# LED_Connectors.net
KiCad netlist of a schematic drawn in Altium Designer
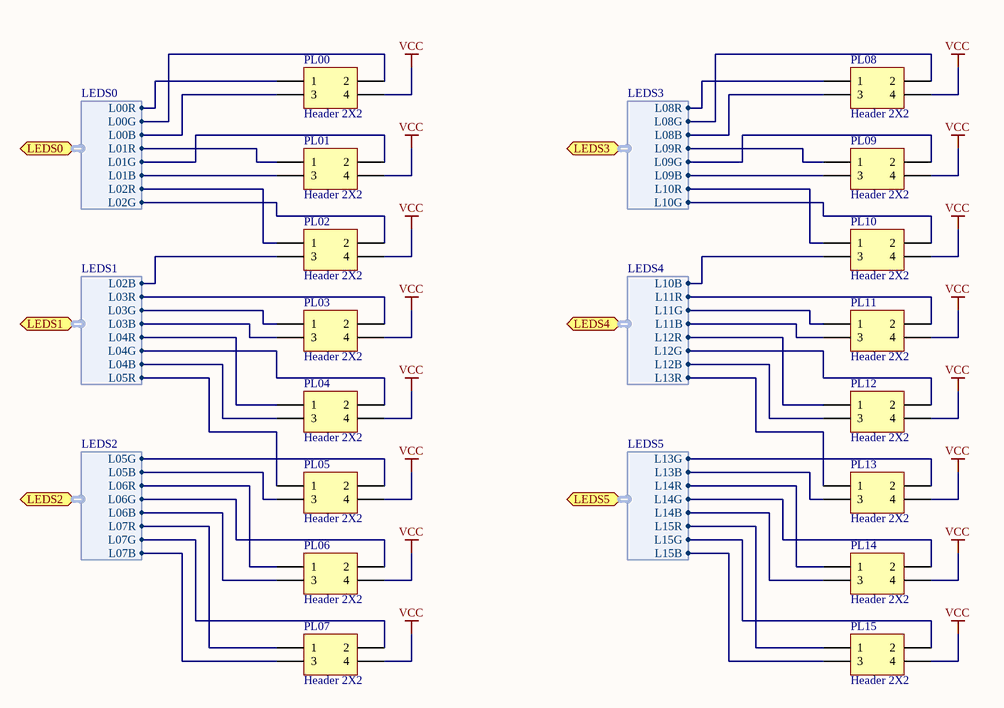
[diagram p0: LED Connectors.SchDoc]

(export (version "E")
  (design (tool "Eeschema 10.0.6"))
  (components
    (comp (ref "PL00")
      (value "Header 2X2")
      (footprint "HDR2X2")
      (description "Header, 2-Pin, Dual row")
      (fields (field (name "PUBLISHER") "Altium Limited"))
      (libsource (lib "Miscellaneous Connectors") (part "Header 2X2"))
    )
    (comp (ref "PL01")
      (value "Header 2X2")
      (footprint "HDR2X2")
      (description "Header, 2-Pin, Dual row")
      (fields (field (name "PUBLISHER") "Altium Limited"))
      (libsource (lib "Miscellaneous Connectors") (part "Header 2X2"))
    )
    (comp (ref "PL02")
      (value "Header 2X2")
      (footprint "HDR2X2")
      (description "Header, 2-Pin, Dual row")
      (fields (field (name "PUBLISHER") "Altium Limited"))
      (libsource (lib "Miscellaneous Connectors") (part "Header 2X2"))
    )
    (comp (ref "PL03")
      (value "Header 2X2")
      (footprint "HDR2X2")
      (description "Header, 2-Pin, Dual row")
      (fields (field (name "PUBLISHER") "Altium Limited"))
      (libsource (lib "Miscellaneous Connectors") (part "Header 2X2"))
    )
    (comp (ref "PL04")
      (value "Header 2X2")
      (footprint "HDR2X2")
      (description "Header, 2-Pin, Dual row")
      (fields (field (name "PUBLISHER") "Altium Limited"))
      (libsource (lib "Miscellaneous Connectors") (part "Header 2X2"))
    )
    (comp (ref "PL05")
      (value "Header 2X2")
      (footprint "HDR2X2")
      (description "Header, 2-Pin, Dual row")
      (fields (field (name "PUBLISHER") "Altium Limited"))
      (libsource (lib "Miscellaneous Connectors") (part "Header 2X2"))
    )
    (comp (ref "PL06")
      (value "Header 2X2")
      (footprint "HDR2X2")
      (description "Header, 2-Pin, Dual row")
      (fields (field (name "PUBLISHER") "Altium Limited"))
      (libsource (lib "Miscellaneous Connectors") (part "Header 2X2"))
    )
    (comp (ref "PL07")
      (value "Header 2X2")
      (footprint "HDR2X2")
      (description "Header, 2-Pin, Dual row")
      (fields (field (name "PUBLISHER") "Altium Limited"))
      (libsource (lib "Miscellaneous Connectors") (part "Header 2X2"))
    )
    (comp (ref "PL08")
      (value "Header 2X2")
      (footprint "HDR2X2")
      (description "Header, 2-Pin, Dual row")
      (fields (field (name "PUBLISHER") "Altium Limited"))
      (libsource (lib "Miscellaneous Connectors") (part "Header 2X2"))
    )
    (comp (ref "PL09")
      (value "Header 2X2")
      (footprint "HDR2X2")
      (description "Header, 2-Pin, Dual row")
      (fields (field (name "PUBLISHER") "Altium Limited"))
      (libsource (lib "Miscellaneous Connectors") (part "Header 2X2"))
    )
    (comp (ref "PL10")
      (value "Header 2X2")
      (footprint "HDR2X2")
      (description "Header, 2-Pin, Dual row")
      (fields (field (name "PUBLISHER") "Altium Limited"))
      (libsource (lib "Miscellaneous Connectors") (part "Header 2X2"))
    )
    (comp (ref "PL11")
      (value "Header 2X2")
      (footprint "HDR2X2")
      (description "Header, 2-Pin, Dual row")
      (fields (field (name "PUBLISHER") "Altium Limited"))
      (libsource (lib "Miscellaneous Connectors") (part "Header 2X2"))
    )
    (comp (ref "PL12")
      (value "Header 2X2")
      (footprint "HDR2X2")
      (description "Header, 2-Pin, Dual row")
      (fields (field (name "PUBLISHER") "Altium Limited"))
      (libsource (lib "Miscellaneous Connectors") (part "Header 2X2"))
    )
    (comp (ref "PL13")
      (value "Header 2X2")
      (footprint "HDR2X2")
      (description "Header, 2-Pin, Dual row")
      (fields (field (name "PUBLISHER") "Altium Limited"))
      (libsource (lib "Miscellaneous Connectors") (part "Header 2X2"))
    )
    (comp (ref "PL14")
      (value "Header 2X2")
      (footprint "HDR2X2")
      (description "Header, 2-Pin, Dual row")
      (fields (field (name "PUBLISHER") "Altium Limited"))
      (libsource (lib "Miscellaneous Connectors") (part "Header 2X2"))
    )
    (comp (ref "PL15")
      (value "Header 2X2")
      (footprint "HDR2X2")
      (description "Header, 2-Pin, Dual row")
      (fields (field (name "PUBLISHER") "Altium Limited"))
      (libsource (lib "Miscellaneous Connectors") (part "Header 2X2"))
    )
  )
  (nets
    (net (code "7") (name "/L00B") (class "Default")
      (node (ref "PL00") (pin "3") (pinfunction "3_3") (pintype "passive"))
    )
    (net (code "8") (name "/L00G") (class "Default")
      (node (ref "PL00") (pin "2") (pinfunction "2_2") (pintype "passive"))
    )
    (net (code "9") (name "/L00R") (class "Default")
      (node (ref "PL00") (pin "1") (pinfunction "1_1") (pintype "passive"))
    )
    (net (code "10") (name "/L01B") (class "Default")
      (node (ref "PL01") (pin "3") (pinfunction "3_3") (pintype "passive"))
    )
    (net (code "11") (name "/L01G") (class "Default")
      (node (ref "PL01") (pin "2") (pinfunction "2_2") (pintype "passive"))
    )
    (net (code "12") (name "/L01R") (class "Default")
      (node (ref "PL01") (pin "1") (pinfunction "1_1") (pintype "passive"))
    )
    (net (code "13") (name "/L02B") (class "Default")
      (node (ref "PL02") (pin "3") (pinfunction "3_3") (pintype "passive"))
    )
    (net (code "14") (name "/L02G") (class "Default")
      (node (ref "PL02") (pin "2") (pinfunction "2_2") (pintype "passive"))
    )
    (net (code "15") (name "/L02R") (class "Default")
      (node (ref "PL02") (pin "1") (pinfunction "1_1") (pintype "passive"))
    )
    (net (code "16") (name "/L03B") (class "Default")
      (node (ref "PL03") (pin "3") (pinfunction "3_3") (pintype "passive"))
    )
    (net (code "17") (name "/L03G") (class "Default")
      (node (ref "PL03") (pin "1") (pinfunction "1_1") (pintype "passive"))
    )
    (net (code "18") (name "/L03R") (class "Default")
      (node (ref "PL03") (pin "2") (pinfunction "2_2") (pintype "passive"))
    )
    (net (code "19") (name "/L04B") (class "Default")
      (node (ref "PL04") (pin "3") (pinfunction "3_3") (pintype "passive"))
    )
    (net (code "20") (name "/L04G") (class "Default")
      (node (ref "PL04") (pin "2") (pinfunction "2_2") (pintype "passive"))
    )
    (net (code "21") (name "/L04R") (class "Default")
      (node (ref "PL04") (pin "1") (pinfunction "1_1") (pintype "passive"))
    )
    (net (code "22") (name "/L05B") (class "Default")
      (node (ref "PL05") (pin "3") (pinfunction "3_3") (pintype "passive"))
    )
    (net (code "23") (name "/L05G") (class "Default")
      (node (ref "PL05") (pin "2") (pinfunction "2_2") (pintype "passive"))
    )
    (net (code "24") (name "/L05R") (class "Default")
      (node (ref "PL05") (pin "1") (pinfunction "1_1") (pintype "passive"))
    )
    (net (code "25") (name "/L06B") (class "Default")
      (node (ref "PL06") (pin "3") (pinfunction "3_3") (pintype "passive"))
    )
    (net (code "26") (name "/L06G") (class "Default")
      (node (ref "PL06") (pin "2") (pinfunction "2_2") (pintype "passive"))
    )
    (net (code "27") (name "/L06R") (class "Default")
      (node (ref "PL06") (pin "1") (pinfunction "1_1") (pintype "passive"))
    )
    (net (code "28") (name "/L07B") (class "Default")
      (node (ref "PL07") (pin "3") (pinfunction "3_3") (pintype "passive"))
    )
    (net (code "29") (name "/L07G") (class "Default")
      (node (ref "PL07") (pin "2") (pinfunction "2_2") (pintype "passive"))
    )
    (net (code "30") (name "/L07R") (class "Default")
      (node (ref "PL07") (pin "1") (pinfunction "1_1") (pintype "passive"))
    )
    (net (code "31") (name "/L08B") (class "Default")
      (node (ref "PL08") (pin "3") (pinfunction "3_3") (pintype "passive"))
    )
    (net (code "32") (name "/L08G") (class "Default")
      (node (ref "PL08") (pin "2") (pinfunction "2_2") (pintype "passive"))
    )
    (net (code "33") (name "/L08R") (class "Default")
      (node (ref "PL08") (pin "1") (pinfunction "1_1") (pintype "passive"))
    )
    (net (code "34") (name "/L09B") (class "Default")
      (node (ref "PL09") (pin "3") (pinfunction "3_3") (pintype "passive"))
    )
    (net (code "35") (name "/L09G") (class "Default")
      (node (ref "PL09") (pin "2") (pinfunction "2_2") (pintype "passive"))
    )
    (net (code "36") (name "/L09R") (class "Default")
      (node (ref "PL09") (pin "1") (pinfunction "1_1") (pintype "passive"))
    )
    (net (code "37") (name "/L10B") (class "Default")
      (node (ref "PL10") (pin "3") (pinfunction "3_3") (pintype "passive"))
    )
    (net (code "38") (name "/L10G") (class "Default")
      (node (ref "PL10") (pin "2") (pinfunction "2_2") (pintype "passive"))
    )
    (net (code "39") (name "/L10R") (class "Default")
      (node (ref "PL10") (pin "1") (pinfunction "1_1") (pintype "passive"))
    )
    (net (code "40") (name "/L11B") (class "Default")
      (node (ref "PL11") (pin "3") (pinfunction "3_3") (pintype "passive"))
    )
    (net (code "41") (name "/L11G") (class "Default")
      (node (ref "PL11") (pin "1") (pinfunction "1_1") (pintype "passive"))
    )
    (net (code "42") (name "/L11R") (class "Default")
      (node (ref "PL11") (pin "2") (pinfunction "2_2") (pintype "passive"))
    )
    (net (code "43") (name "/L12B") (class "Default")
      (node (ref "PL12") (pin "3") (pinfunction "3_3") (pintype "passive"))
    )
    (net (code "44") (name "/L12G") (class "Default")
      (node (ref "PL12") (pin "2") (pinfunction "2_2") (pintype "passive"))
    )
    (net (code "45") (name "/L12R") (class "Default")
      (node (ref "PL12") (pin "1") (pinfunction "1_1") (pintype "passive"))
    )
    (net (code "46") (name "/L13B") (class "Default")
      (node (ref "PL13") (pin "3") (pinfunction "3_3") (pintype "passive"))
    )
    (net (code "47") (name "/L13G") (class "Default")
      (node (ref "PL13") (pin "2") (pinfunction "2_2") (pintype "passive"))
    )
    (net (code "48") (name "/L13R") (class "Default")
      (node (ref "PL13") (pin "1") (pinfunction "1_1") (pintype "passive"))
    )
    (net (code "49") (name "/L14B") (class "Default")
      (node (ref "PL14") (pin "3") (pinfunction "3_3") (pintype "passive"))
    )
    (net (code "50") (name "/L14G") (class "Default")
      (node (ref "PL14") (pin "2") (pinfunction "2_2") (pintype "passive"))
    )
    (net (code "51") (name "/L14R") (class "Default")
      (node (ref "PL14") (pin "1") (pinfunction "1_1") (pintype "passive"))
    )
    (net (code "52") (name "/L15B") (class "Default")
      (node (ref "PL15") (pin "3") (pinfunction "3_3") (pintype "passive"))
    )
    (net (code "53") (name "/L15G") (class "Default")
      (node (ref "PL15") (pin "2") (pinfunction "2_2") (pintype "passive"))
    )
    (net (code "54") (name "/L15R") (class "Default")
      (node (ref "PL15") (pin "1") (pinfunction "1_1") (pintype "passive"))
    )
    (net (code "61") (name "VCC") (class "Default")
      (node (ref "PL00") (pin "4") (pinfunction "4_4") (pintype "passive"))
      (node (ref "PL01") (pin "4") (pinfunction "4_4") (pintype "passive"))
      (node (ref "PL02") (pin "4") (pinfunction "4_4") (pintype "passive"))
      (node (ref "PL03") (pin "4") (pinfunction "4_4") (pintype "passive"))
      (node (ref "PL04") (pin "4") (pinfunction "4_4") (pintype "passive"))
      (node (ref "PL05") (pin "4") (pinfunction "4_4") (pintype "passive"))
      (node (ref "PL06") (pin "4") (pinfunction "4_4") (pintype "passive"))
      (node (ref "PL07") (pin "4") (pinfunction "4_4") (pintype "passive"))
      (node (ref "PL08") (pin "4") (pinfunction "4_4") (pintype "passive"))
      (node (ref "PL09") (pin "4") (pinfunction "4_4") (pintype "passive"))
      (node (ref "PL10") (pin "4") (pinfunction "4_4") (pintype "passive"))
      (node (ref "PL11") (pin "4") (pinfunction "4_4") (pintype "passive"))
      (node (ref "PL12") (pin "4") (pinfunction "4_4") (pintype "passive"))
      (node (ref "PL13") (pin "4") (pinfunction "4_4") (pintype "passive"))
      (node (ref "PL14") (pin "4") (pinfunction "4_4") (pintype "passive"))
      (node (ref "PL15") (pin "4") (pinfunction "4_4") (pintype "passive"))
    )
  )
)
